# design.net
KiCad netlist of a schematic drawn in Altium Designer
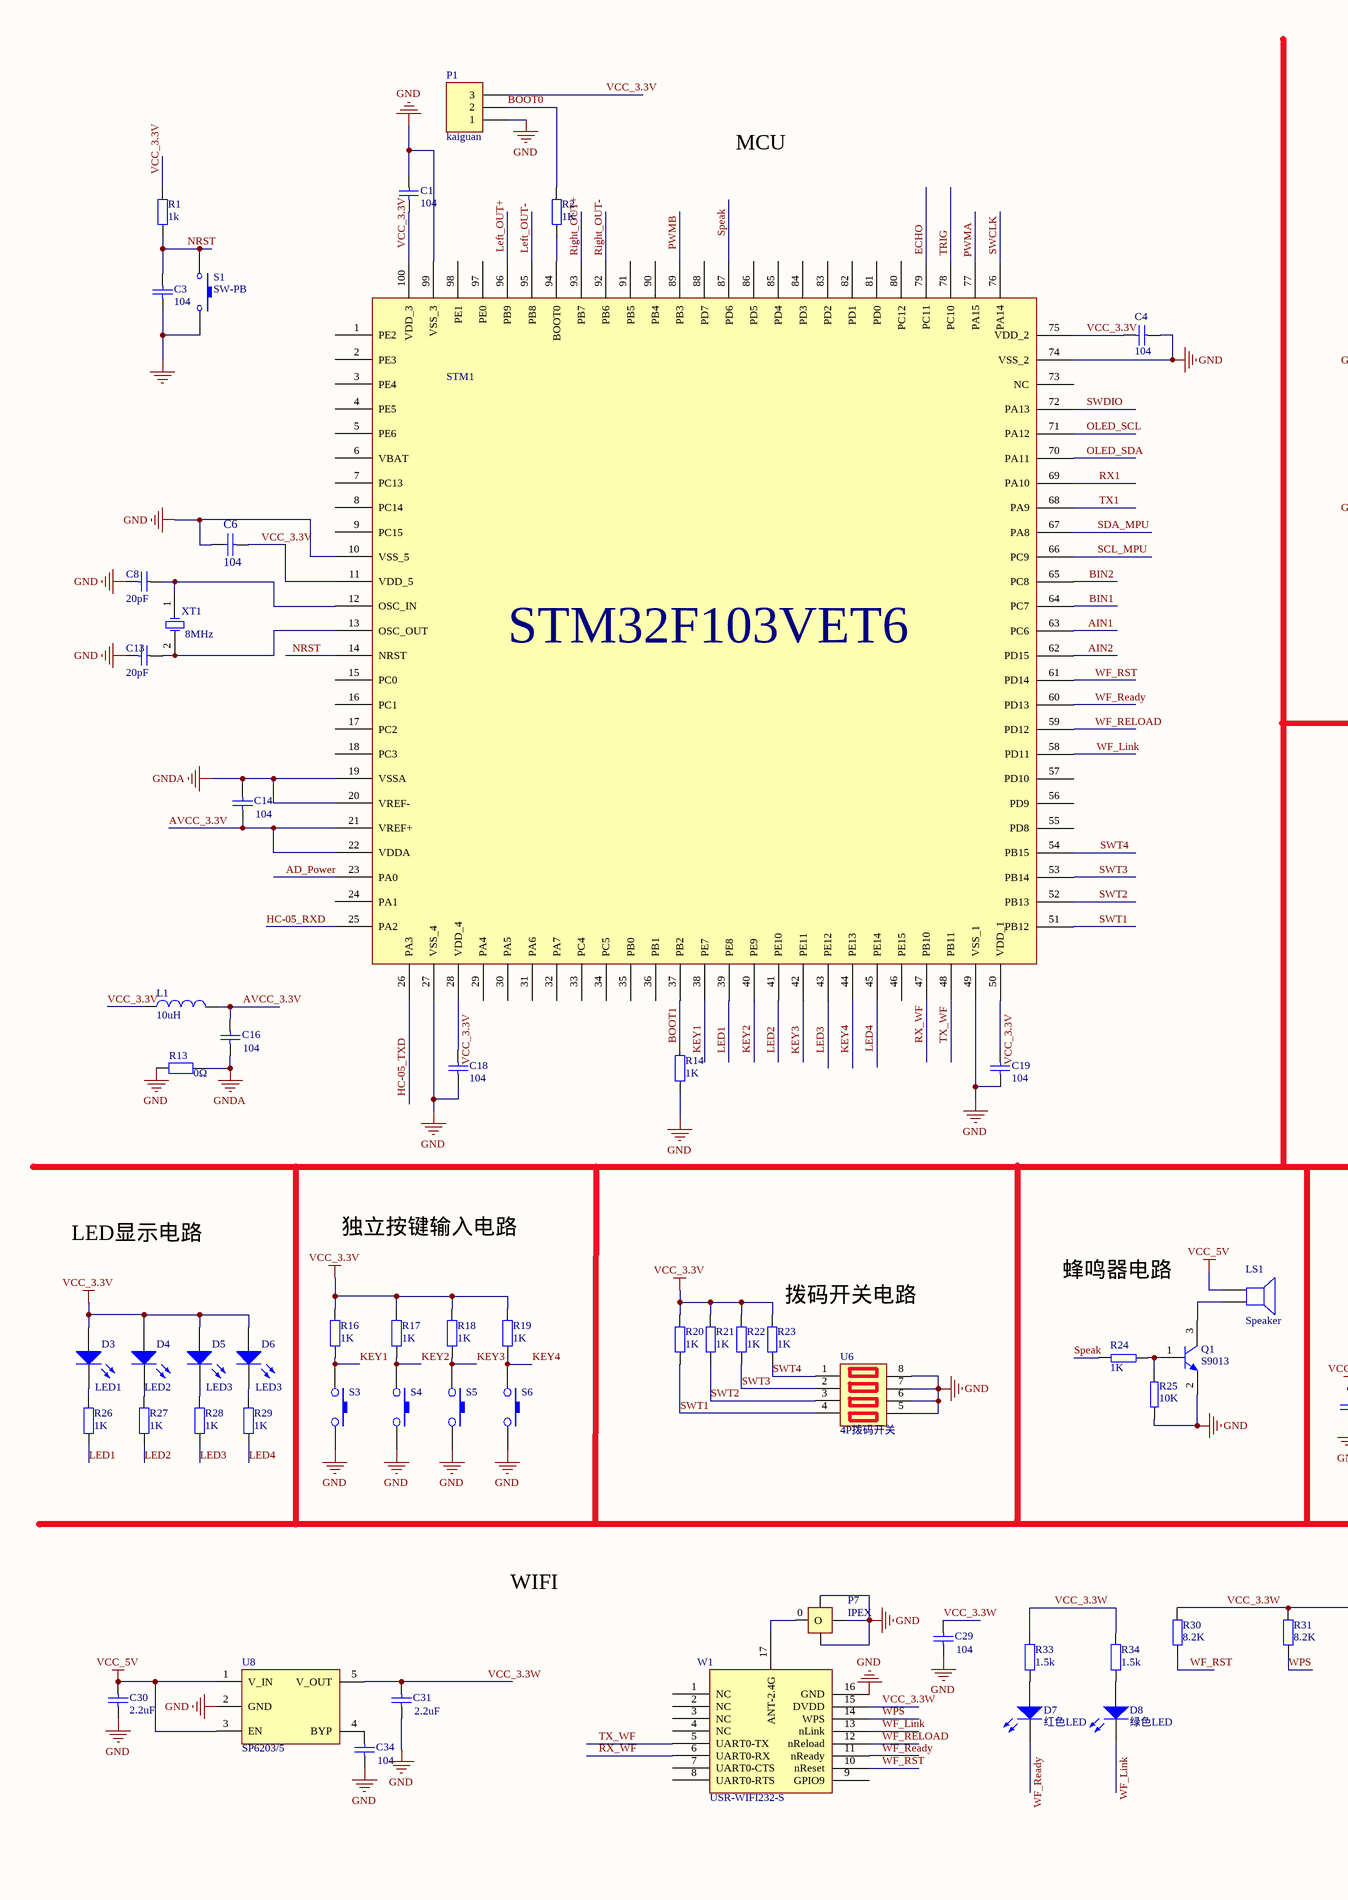
[diagram p0: 平衡车.SchDoc, left]
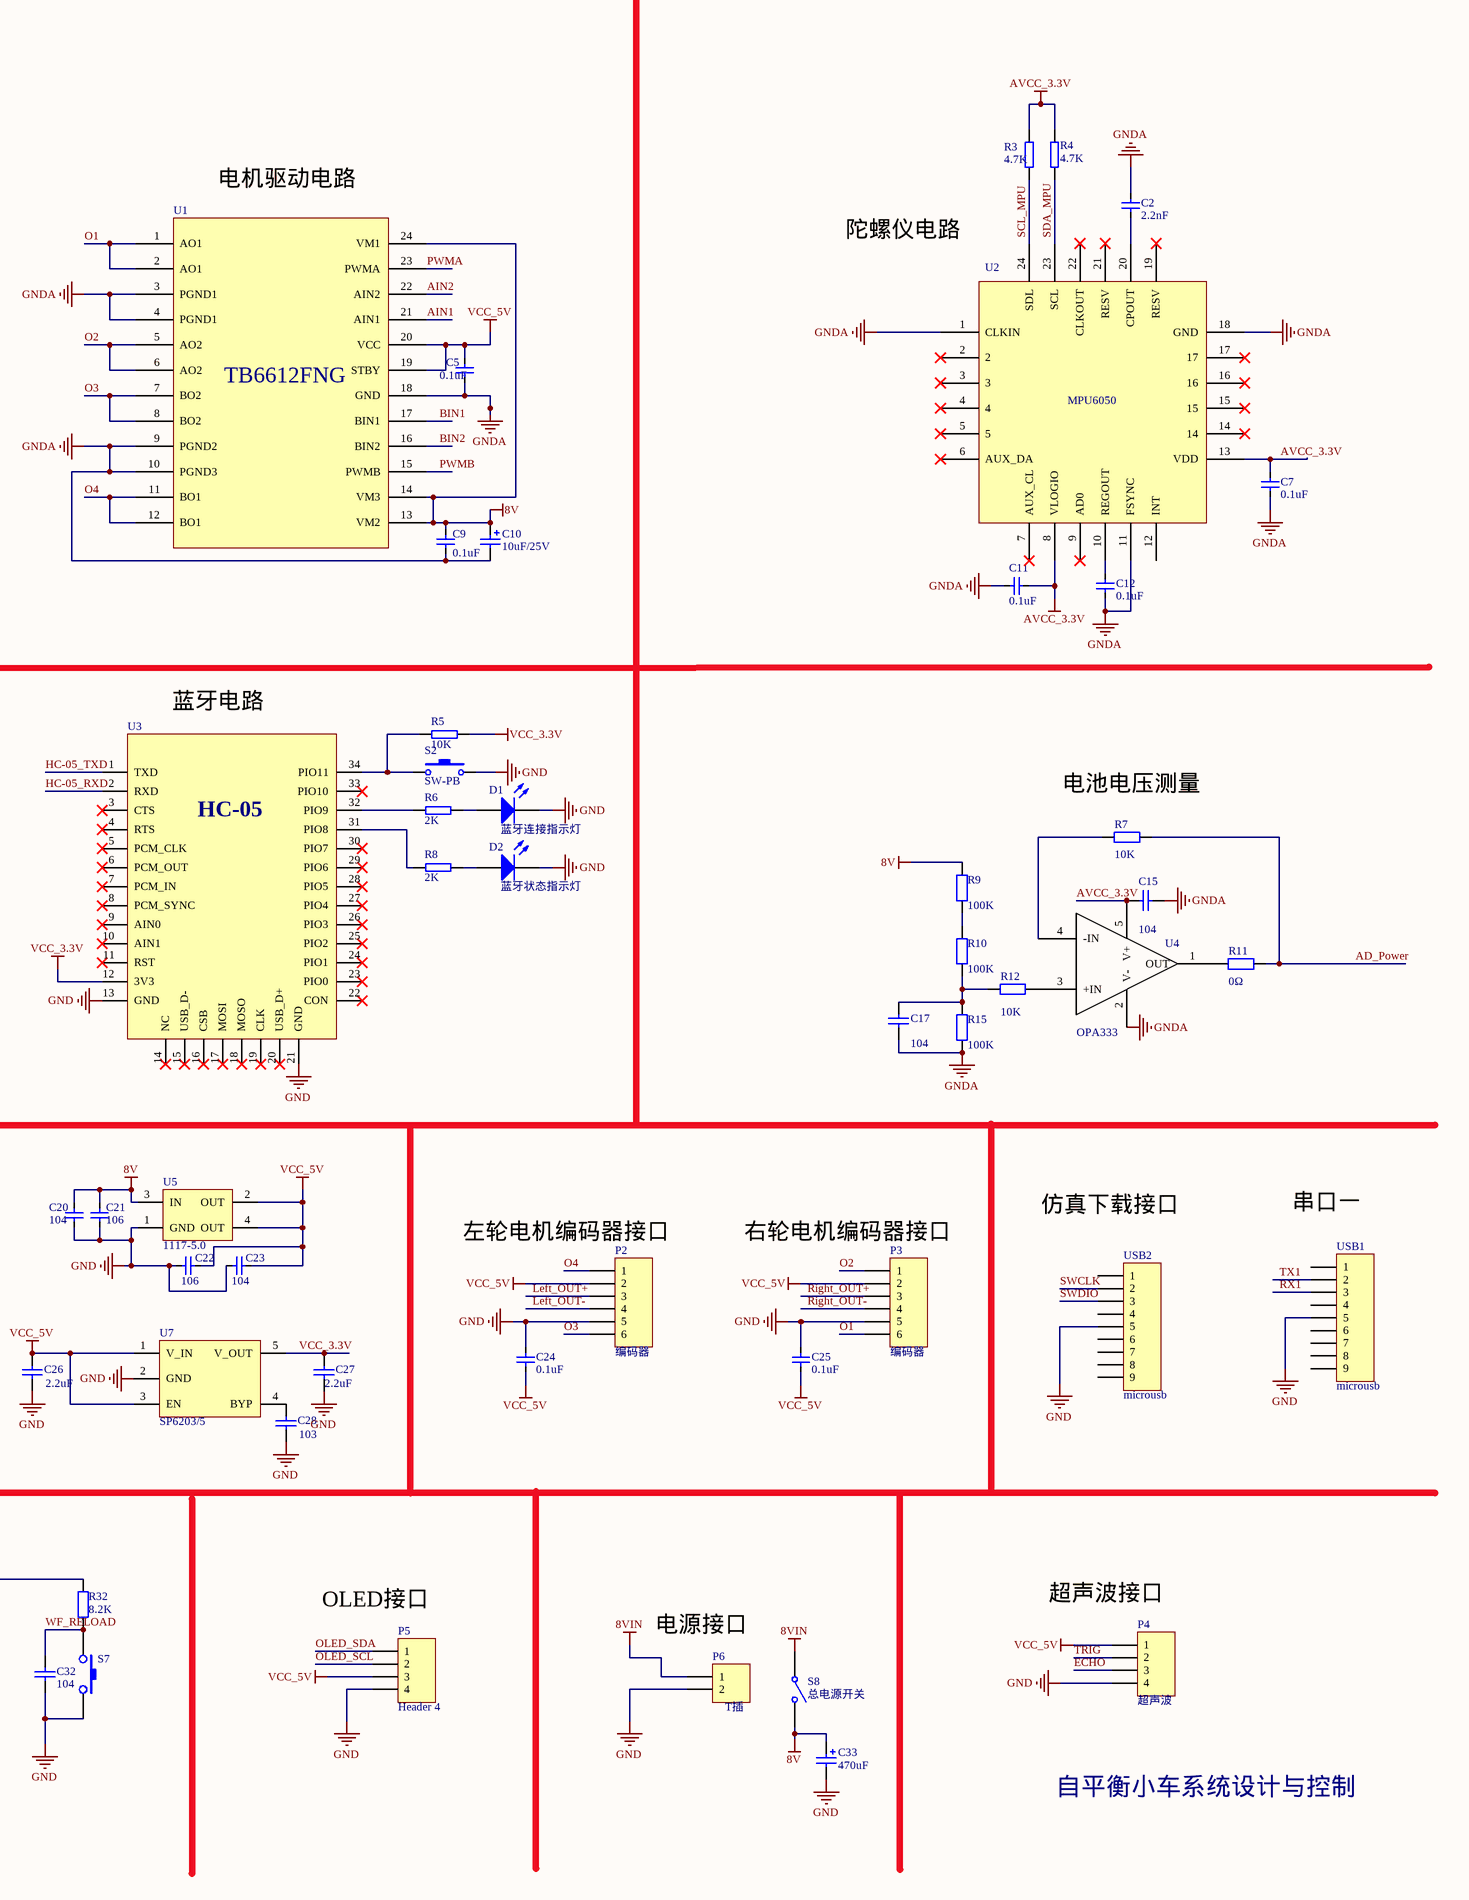
[diagram p1: 平衡车.SchDoc, right]

(export (version "E")
  (design (tool "Eeschema 10.0.6"))
  (components
    (comp (ref "C1")
      (value "104")
      (footprint "0603电容")
      (description "Capacitor")
      (fields (field (name "PUBLISHER") "Altium Limited"))
      (libsource (lib "Miscellaneous Devices") (part "Cap"))
    )
    (comp (ref "C2")
      (value "CAP_2.2nf")
      (footprint "0603电容")
      (fields (field (name "ALTIUM_UNNAMED_1") "2.2nF"))
      (libsource (lib "STM32F103C8T6最小系统") (part "CAP_22"))
    )
    (comp (ref "C3")
      (value "104")
      (footprint "0603电容")
      (description "Capacitor")
      (fields (field (name "PUBLISHER") "Altium Limited"))
      (libsource (lib "Miscellaneous Devices") (part "Cap"))
    )
    (comp (ref "C4")
      (value "104")
      (footprint "0603电容")
      (description "Capacitor")
      (fields (field (name "PUBLISHER") "Altium Limited"))
      (libsource (lib "Miscellaneous Devices") (part "Cap"))
    )
    (comp (ref "C5")
      (value "CAP_104")
      (footprint "0603电容")
      (fields (field (name "ALTIUM_UNNAMED_1") "0.1uF"))
      (libsource (lib "STM32F103C8T6最小系统") (part "CAP_22"))
    )
    (comp (ref "C6") (value "104") (footprint "0603电容") (libsource (lib "*") (part "ProA111.TMP_30p_6")))
    (comp (ref "C7")
      (value "CAP_104")
      (footprint "0603电容")
      (fields (field (name "ALTIUM_UNNAMED_1") "0.1uF"))
      (libsource (lib "STM32F103C8T6最小系统") (part "CAP_22"))
    )
    (comp (ref "C8")
      (value "20pF")
      (footprint "0603电容")
      (description "Capacitor")
      (fields (field (name "PUBLISHER") "Altium Limited"))
      (libsource (lib "Miscellaneous Devices") (part "Cap"))
    )
    (comp (ref "C9")
      (value "CAP_104")
      (footprint "0603电容")
      (fields (field (name "ALTIUM_UNNAMED_1") "0.1uF"))
      (libsource (lib "STM32F103C8T6最小系统") (part "CAP_22"))
    )
    (comp (ref "C10")
      (value "10uF/25V")
      (footprint "C型钽电容")
      (description "Polarized Capacitor (Axial)")
      (fields (field (name "Comment") "Cap Pol2") (field (name "PUBLISHER") "Altium Limited"))
      (libsource (lib "Miscellaneous Devices") (part "Cap Pol2"))
    )
    (comp (ref "C11")
      (value "CAP_104")
      (footprint "0603电容")
      (fields (field (name "ALTIUM_UNNAMED_1") "0.1uF"))
      (libsource (lib "STM32F103C8T6最小系统") (part "CAP_22"))
    )
    (comp (ref "C12")
      (value "CAP_104")
      (footprint "0603电容")
      (fields (field (name "ALTIUM_UNNAMED_1") "0.1uF"))
      (libsource (lib "STM32F103C8T6最小系统") (part "CAP_22"))
    )
    (comp (ref "C13")
      (value "20pF")
      (footprint "0603电容")
      (description "Capacitor")
      (fields (field (name "PUBLISHER") "Altium Limited"))
      (libsource (lib "Miscellaneous Devices") (part "Cap"))
    )
    (comp (ref "C14")
      (value "104")
      (footprint "0603电容")
      (description "Capacitor")
      (fields (field (name "PUBLISHER") "Altium Limited"))
      (libsource (lib "Miscellaneous Devices") (part "Cap"))
    )
    (comp (ref "C15")
      (value "104")
      (footprint "0603电容")
      (description "Capacitor")
      (fields (field (name "PUBLISHER") "Altium Limited"))
      (libsource (lib "Miscellaneous Devices") (part "Cap"))
    )
    (comp (ref "C16")
      (value "104")
      (footprint "0603电容")
      (description "Capacitor")
      (fields (field (name "PUBLISHER") "Altium Limited"))
      (libsource (lib "Miscellaneous Devices") (part "Cap"))
    )
    (comp (ref "C17")
      (value "104")
      (footprint "0603电容")
      (description "Capacitor")
      (fields (field (name "PUBLISHER") "Altium Limited"))
      (libsource (lib "Miscellaneous Devices") (part "Cap"))
    )
    (comp (ref "C18")
      (value "104")
      (footprint "0603电容")
      (description "Capacitor")
      (fields (field (name "PUBLISHER") "Altium Limited"))
      (libsource (lib "Miscellaneous Devices") (part "Cap"))
    )
    (comp (ref "C19")
      (value "104")
      (footprint "0603电容")
      (description "Capacitor")
      (fields (field (name "PUBLISHER") "Altium Limited"))
      (libsource (lib "Miscellaneous Devices") (part "Cap"))
    )
    (comp (ref "C20")
      (value "CAP_104")
      (footprint "0603电容")
      (fields (field (name "ALTIUM_UNNAMED_1") "104"))
      (libsource (lib "STM32F103C8T6最小系统") (part "CAP_22"))
    )
    (comp (ref "C21")
      (value "CAP_104")
      (footprint "0603电容")
      (fields (field (name "ALTIUM_UNNAMED_1") "106"))
      (libsource (lib "STM32F103C8T6最小系统") (part "CAP_22"))
    )
    (comp (ref "C22")
      (value "CAP_104")
      (footprint "0603电容")
      (fields (field (name "ALTIUM_UNNAMED_1") "106"))
      (libsource (lib "STM32F103C8T6最小系统") (part "CAP_22"))
    )
    (comp (ref "C23")
      (value "CAP_104")
      (footprint "0603电容")
      (fields (field (name "ALTIUM_UNNAMED_1") "104"))
      (libsource (lib "STM32F103C8T6最小系统") (part "CAP_22"))
    )
    (comp (ref "C24")
      (value "CAP_104")
      (footprint "0603电容")
      (fields (field (name "ALTIUM_UNNAMED_1") "0.1uF"))
      (libsource (lib "STM32F103C8T6最小系统") (part "CAP_22"))
    )
    (comp (ref "C25")
      (value "CAP_104")
      (footprint "0603电容")
      (fields (field (name "ALTIUM_UNNAMED_1") "0.1uF"))
      (libsource (lib "STM32F103C8T6最小系统") (part "CAP_22"))
    )
    (comp (ref "C26")
      (value "2.2uF")
      (footprint "0603电容")
      (description "Capacitor")
      (fields (field (name "PUBLISHER") "Altium Limited"))
      (libsource (lib "Miscellaneous Devices") (part "Cap"))
    )
    (comp (ref "C27")
      (value "2.2uF")
      (footprint "0603电容")
      (description "Capacitor")
      (fields (field (name "PUBLISHER") "Altium Limited"))
      (libsource (lib "Miscellaneous Devices") (part "Cap"))
    )
    (comp (ref "C28")
      (value "103")
      (footprint "0603电容")
      (description "Capacitor")
      (fields (field (name "PUBLISHER") "Altium Limited"))
      (libsource (lib "Miscellaneous Devices") (part "Cap"))
    )
    (comp (ref "C29")
      (value "104")
      (footprint "0603电容")
      (description "Capacitor")
      (fields (field (name "PUBLISHER") "Altium Limited"))
      (libsource (lib "Miscellaneous Devices") (part "Cap"))
    )
    (comp (ref "C30")
      (value "2.2uF")
      (footprint "0603电容")
      (description "Capacitor")
      (fields (field (name "PUBLISHER") "Altium Limited"))
      (libsource (lib "Miscellaneous Devices") (part "Cap"))
    )
    (comp (ref "C31")
      (value "2.2uF")
      (footprint "0603电容")
      (description "Capacitor")
      (fields (field (name "PUBLISHER") "Altium Limited"))
      (libsource (lib "Miscellaneous Devices") (part "Cap"))
    )
    (comp (ref "C32")
      (value "104")
      (footprint "0603电容")
      (description "Capacitor")
      (fields (field (name "PUBLISHER") "Altium Limited"))
      (libsource (lib "Miscellaneous Devices") (part "Cap"))
    )
    (comp (ref "C33")
      (value "470uF")
      (footprint "470uF")
      (description "Polarized Capacitor (Axial)")
      (fields (field (name "Comment") "Cap Pol2") (field (name "PUBLISHER") "Altium Limited"))
      (libsource (lib "Miscellaneous Devices") (part "Cap Pol2"))
    )
    (comp (ref "C34")
      (value "104")
      (footprint "0603电容")
      (description "Capacitor")
      (fields (field (name "PUBLISHER") "Altium Limited"))
      (libsource (lib "Miscellaneous Devices") (part "Cap"))
    )
    (comp (ref "D1")
      (value "蓝牙连接指示灯")
      (footprint "0603LED红色")
      (description "Typical INFRARED GaAs LED")
      (fields (field (name "PUBLISHER") "Altium Limited"))
      (libsource (lib "Miscellaneous Devices") (part "LED0"))
    )
    (comp (ref "D2")
      (value "蓝牙状态指示灯")
      (footprint "0603LED绿色")
      (description "Typical INFRARED GaAs LED")
      (fields (field (name "PUBLISHER") "Altium Limited"))
      (libsource (lib "Miscellaneous Devices") (part "LED0"))
    )
    (comp (ref "D3")
      (value "LED1")
      (footprint "0603LED红色")
      (description "Typical INFRARED GaAs LED")
      (fields (field (name "PUBLISHER") "Altium Limited"))
      (libsource (lib "Miscellaneous Devices") (part "LED0"))
    )
    (comp (ref "D4")
      (value "LED2")
      (footprint "0603LED红色")
      (description "Typical INFRARED GaAs LED")
      (fields (field (name "PUBLISHER") "Altium Limited"))
      (libsource (lib "Miscellaneous Devices") (part "LED0"))
    )
    (comp (ref "D5")
      (value "LED3")
      (footprint "0603LED红色")
      (description "Typical INFRARED GaAs LED")
      (fields (field (name "PUBLISHER") "Altium Limited"))
      (libsource (lib "Miscellaneous Devices") (part "LED0"))
    )
    (comp (ref "D6")
      (value "LED3")
      (footprint "0603LED红色")
      (description "Typical INFRARED GaAs LED")
      (fields (field (name "PUBLISHER") "Altium Limited"))
      (libsource (lib "Miscellaneous Devices") (part "LED0"))
    )
    (comp (ref "D7")
      (value "红色LED")
      (footprint "0603LED红色")
      (description "Typical INFRARED GaAs LED")
      (fields (field (name "PUBLISHER") "Altium Limited"))
      (libsource (lib "Miscellaneous Devices") (part "LED0"))
    )
    (comp (ref "D8")
      (value "绿色LED")
      (footprint "0603LED绿色")
      (description "Typical INFRARED GaAs LED")
      (fields (field (name "PUBLISHER") "Altium Limited"))
      (libsource (lib "Miscellaneous Devices") (part "LED0"))
    )
    (comp (ref "L1")
      (value "10uH")
      (footprint "电感")
      (description "Inductor")
      (fields (field (name "PUBLISHER") "Altium Limited"))
      (libsource (lib "Miscellaneous Devices") (part "Inductor"))
    )
    (comp (ref "LS1")
      (value "Speaker")
      (footprint "孔距5mm蜂鸣器")
      (description "Loudspeaker")
      (fields (field (name "PUBLISHER") "Altium Limited"))
      (libsource (lib "Miscellaneous Devices") (part "Speaker"))
    )
    (comp (ref "P1")
      (value "kaiguan")
      (footprint "HDR1X3")
      (description "Header, 3-Pin")
      (fields (field (name "PUBLISHER") "Altium Limited"))
      (libsource (lib "Miscellaneous Connectors") (part "Header 3"))
    )
    (comp (ref "P2")
      (value "编码器")
      (footprint "6P带锁插针底座")
      (description "Header, 6-Pin")
      (fields (field (name "PUBLISHER") "Altium Limited"))
      (libsource (lib "Miscellaneous Connectors") (part "Header 6"))
    )
    (comp (ref "P3")
      (value "编码器")
      (footprint "6P带锁插针底座")
      (description "Header, 6-Pin")
      (fields (field (name "PUBLISHER") "Altium Limited"))
      (libsource (lib "Miscellaneous Connectors") (part "Header 6"))
    )
    (comp (ref "P4")
      (value "超声波")
      (footprint "四脚底座")
      (description "Header, 4-Pin")
      (fields (field (name "PUBLISHER") "Altium Limited"))
      (libsource (lib "Miscellaneous Connectors") (part "Header 4"))
    )
    (comp (ref "P5")
      (value "Header 4")
      (footprint "四脚底座_液晶")
      (description "Header, 4-Pin")
      (fields (field (name "PUBLISHER") "Altium Limited"))
      (libsource (lib "Miscellaneous Connectors") (part "Header 4"))
    )
    (comp (ref "P6")
      (value "T插")
      (footprint "电源底座")
      (description "Header, 2-Pin")
      (fields (field (name "PUBLISHER") "Altium Limited"))
      (libsource (lib "Miscellaneous Connectors") (part "Header 2"))
    )
    (comp (ref "P7") (value "IPEX") (footprint "天线底座") (libsource (lib "WZJ_SchLib") (part "IPEX")))
    (comp (ref "Q1") (value "S9013") (footprint "S8050贴片三极管") (libsource (lib "WZJ_SchLib") (part "S9013_s")))
    (comp (ref "R1")
      (value "1k")
      (footprint "0603电阻")
      (description "Resistor")
      (fields (field (name "PUBLISHER") "Altium Limited"))
      (libsource (lib "Miscellaneous Devices") (part "Res2"))
    )
    (comp (ref "R2")
      (value "1K")
      (footprint "0603电阻")
      (description "Resistor")
      (fields (field (name "PUBLISHER") "Altium Limited"))
      (libsource (lib "Miscellaneous Devices") (part "Res2"))
    )
    (comp (ref "R3")
      (value "RES_10K")
      (footprint "0603电阻")
      (fields (field (name "ALTIUM_UNNAMED_1") "4.7K"))
      (libsource (lib "STM32F103C8T6最小系统") (part "RES_10K"))
    )
    (comp (ref "R4")
      (value "RES_10K")
      (footprint "0603电阻")
      (fields (field (name "ALTIUM_UNNAMED_1") "4.7K"))
      (libsource (lib "STM32F103C8T6最小系统") (part "RES_10K"))
    )
    (comp (ref "R5")
      (value "RES_10K")
      (footprint "0603电阻")
      (fields (field (name "ALTIUM_UNNAMED_1") "10K"))
      (libsource (lib "STM32F103C8T6最小系统") (part "RES_10K"))
    )
    (comp (ref "R6")
      (value "RES_10K")
      (footprint "0603电阻")
      (fields (field (name "ALTIUM_UNNAMED_1") "2K"))
      (libsource (lib "STM32F103C8T6最小系统") (part "RES_10K"))
    )
    (comp (ref "R7")
      (value "10K")
      (footprint "0603电阻")
      (description "Resistor")
      (fields (field (name "PUBLISHER") "Altium Limited"))
      (libsource (lib "") (part "Res2_2"))
    )
    (comp (ref "R8")
      (value "RES_10K")
      (footprint "0603电阻")
      (fields (field (name "ALTIUM_UNNAMED_1") "2K"))
      (libsource (lib "STM32F103C8T6最小系统") (part "RES_10K"))
    )
    (comp (ref "R9")
      (value "100K")
      (footprint "0603电阻")
      (description "Resistor")
      (fields (field (name "PUBLISHER") "Altium Limited"))
      (libsource (lib "") (part "Res2_1"))
    )
    (comp (ref "R10")
      (value "100K")
      (footprint "0603电阻")
      (description "Resistor")
      (fields (field (name "PUBLISHER") "Altium Limited"))
      (libsource (lib "") (part "Res2_1"))
    )
    (comp (ref "R11")
      (value "0Ω")
      (footprint "0603电阻")
      (description "Resistor")
      (fields (field (name "PUBLISHER") "Altium Limited"))
      (libsource (lib "") (part "Res2_2"))
    )
    (comp (ref "R12")
      (value "10K")
      (footprint "0603电阻")
      (description "Resistor")
      (fields (field (name "PUBLISHER") "Altium Limited"))
      (libsource (lib "") (part "Res2_2"))
    )
    (comp (ref "R13")
      (value "0Ω")
      (footprint "0603电阻")
      (description "Resistor")
      (fields (field (name "PUBLISHER") "Altium Limited"))
      (libsource (lib "") (part "Res2_2"))
    )
    (comp (ref "R14")
      (value "1K")
      (footprint "0603电阻")
      (description "Resistor")
      (fields (field (name "PUBLISHER") "Altium Limited"))
      (libsource (lib "Miscellaneous Devices") (part "Res2"))
    )
    (comp (ref "R15")
      (value "100K")
      (footprint "0603电阻")
      (description "Resistor")
      (fields (field (name "PUBLISHER") "Altium Limited"))
      (libsource (lib "") (part "Res2_1"))
    )
    (comp (ref "R16")
      (value "1K")
      (footprint "0603电阻")
      (description "Resistor")
      (fields (field (name "PUBLISHER") "Altium Limited"))
      (libsource (lib "") (part "Res2_1"))
    )
    (comp (ref "R17")
      (value "1K")
      (footprint "0603电阻")
      (description "Resistor")
      (fields (field (name "PUBLISHER") "Altium Limited"))
      (libsource (lib "") (part "Res2_1"))
    )
    (comp (ref "R18")
      (value "1K")
      (footprint "0603电阻")
      (description "Resistor")
      (fields (field (name "PUBLISHER") "Altium Limited"))
      (libsource (lib "") (part "Res2_1"))
    )
    (comp (ref "R19")
      (value "1K")
      (footprint "0603电阻")
      (description "Resistor")
      (fields (field (name "PUBLISHER") "Altium Limited"))
      (libsource (lib "Miscellaneous Devices") (part "Res2"))
    )
    (comp (ref "R20")
      (value "1K")
      (footprint "0603电阻")
      (description "Resistor")
      (fields (field (name "PUBLISHER") "Altium Limited"))
      (libsource (lib "") (part "Res2_1"))
    )
    (comp (ref "R21")
      (value "1K")
      (footprint "0603电阻")
      (description "Resistor")
      (fields (field (name "PUBLISHER") "Altium Limited"))
      (libsource (lib "") (part "Res2_1"))
    )
    (comp (ref "R22")
      (value "1K")
      (footprint "0603电阻")
      (description "Resistor")
      (fields (field (name "PUBLISHER") "Altium Limited"))
      (libsource (lib "") (part "Res2_1"))
    )
    (comp (ref "R23")
      (value "1K")
      (footprint "0603电阻")
      (description "Resistor")
      (fields (field (name "PUBLISHER") "Altium Limited"))
      (libsource (lib "Miscellaneous Devices") (part "Res2"))
    )
    (comp (ref "R24")
      (value "RES_10K")
      (footprint "0603电阻")
      (fields (field (name "ALTIUM_UNNAMED_1") "1K"))
      (libsource (lib "STM32F103C8T6最小系统") (part "RES_10K"))
    )
    (comp (ref "R25")
      (value "RES_10K")
      (footprint "0603电阻")
      (fields (field (name "ALTIUM_UNNAMED_1") "10K"))
      (libsource (lib "STM32F103C8T6最小系统") (part "RES_10K"))
    )
    (comp (ref "R26")
      (value "1K")
      (footprint "0603电阻")
      (description "Resistor")
      (fields (field (name "PUBLISHER") "Altium Limited"))
      (libsource (lib "") (part "Res2_1"))
    )
    (comp (ref "R27")
      (value "1K")
      (footprint "0603电阻")
      (description "Resistor")
      (fields (field (name "PUBLISHER") "Altium Limited"))
      (libsource (lib "") (part "Res2_1"))
    )
    (comp (ref "R28")
      (value "1K")
      (footprint "0603电阻")
      (description "Resistor")
      (fields (field (name "PUBLISHER") "Altium Limited"))
      (libsource (lib "") (part "Res2_1"))
    )
    (comp (ref "R29")
      (value "1K")
      (footprint "0603电阻")
      (description "Resistor")
      (fields (field (name "PUBLISHER") "Altium Limited"))
      (libsource (lib "") (part "Res2_1"))
    )
    (comp (ref "R30")
      (value "8.2K")
      (footprint "0603电阻")
      (description "Resistor")
      (fields (field (name "PUBLISHER") "Altium Limited"))
      (libsource (lib "Miscellaneous Devices") (part "Res2"))
    )
    (comp (ref "R31")
      (value "8.2K")
      (footprint "0603电阻")
      (description "Resistor")
      (fields (field (name "PUBLISHER") "Altium Limited"))
      (libsource (lib "Miscellaneous Devices") (part "Res2"))
    )
    (comp (ref "R32")
      (value "8.2K")
      (footprint "0603电阻")
      (description "Resistor")
      (fields (field (name "PUBLISHER") "Altium Limited"))
      (libsource (lib "Miscellaneous Devices") (part "Res2"))
    )
    (comp (ref "R33")
      (value "1.5k")
      (footprint "0603电阻")
      (description "Resistor")
      (fields (field (name "PUBLISHER") "Altium Limited"))
      (libsource (lib "") (part "Res2_1"))
    )
    (comp (ref "R34")
      (value "1.5k")
      (footprint "0603电阻")
      (description "Resistor")
      (fields (field (name "PUBLISHER") "Altium Limited"))
      (libsource (lib "") (part "Res2_1"))
    )
    (comp (ref "S1")
      (value "SW-PB")
      (footprint "贴片按键")
      (description "Switch")
      (fields (field (name "PUBLISHER") "Altium Limited"))
      (libsource (lib "Miscellaneous Devices") (part "SW-PB"))
    )
    (comp (ref "S2")
      (value "SW-PB")
      (footprint "贴片按键")
      (description "Switch")
      (fields (field (name "PUBLISHER") "Altium Limited"))
      (libsource (lib "SCH_Switch") (part "SW-PB"))
    )
    (comp (ref "S3") (value "SW-PB") (footprint "贴片按键") (libsource (lib "STM32F103C8T6最小系统") (part "SW-PB")))
    (comp (ref "S4") (value "SW-PB") (footprint "贴片按键") (libsource (lib "STM32F103C8T6最小系统") (part "SW-PB")))
    (comp (ref "S5") (value "SW-PB") (footprint "贴片按键") (libsource (lib "STM32F103C8T6最小系统") (part "SW-PB")))
    (comp (ref "S6") (value "SW-PB") (footprint "贴片按键") (libsource (lib "STM32F103C8T6最小系统") (part "SW-PB")))
    (comp (ref "S7") (value "SW-PB") (footprint "贴片按键") (libsource (lib "STM32F103C8T6最小系统") (part "SW-PB")))
    (comp (ref "S8")
      (value "总电源开关")
      (footprint "纽子开关")
      (description "Single-Pole, Single-Throw Switch")
      (fields (field (name "PUBLISHER") "Altium Limited"))
      (libsource (lib "Miscellaneous Devices") (part "SW-SPST"))
    )
    (comp (ref "STM1")
      (value "STM32F103VET6")
      (footprint "LQFP 100")
      (libsource (lib "WZJ_SchLib") (part "STM32F103VET6"))
    )
    (comp (ref "U1")
      (value "TB6612FNG")
      (footprint "TB6612")
      (libsource (lib "xl_lib_v_1") (part "TB6612FNG"))
    )
    (comp (ref "U2")
      (value "MPU6050")
      (footprint "MPU6050_3mm")
      (libsource (lib "xl_lib_v_1") (part "MPU6050"))
    )
    (comp (ref "U3") (value "HC-05蓝牙") (footprint "HC-05蓝牙邮票孔") (libsource (lib "自平衡小车") (part "HC-05蓝牙")))
    (comp (ref "U4") (value "OPA333") (footprint "LM2735") (libsource (lib "WZJ_SchLib") (part "OPA333")))
    (comp (ref "U5") (value "1117-5.0") (footprint "1117稳压") (libsource (lib "自平衡小车") (part "1117")))
    (comp (ref "U6") (value "4P拨码开关") (footprint "4P贴片拨码开关") (libsource (lib "我的大学四年自画AD库") (part "4P拨码开关")))
    (comp (ref "U7") (value "SP6203/5") (footprint "LM2735") (libsource (lib "WZJ_SchLib") (part "SP6203/5")))
    (comp (ref "U8") (value "SP6203/5") (footprint "LM2735") (libsource (lib "WZJ_SchLib") (part "SP6203/5")))
    (comp (ref "USB1")
      (value "microusb")
      (footprint "Microusb")
      (description "Header, 9-Pin")
      (fields (field (name "PUBLISHER") "Altium Limited"))
      (libsource (lib "Miscellaneous Connectors") (part "Header 9"))
    )
    (comp (ref "USB2")
      (value "microusb")
      (footprint "Microusb")
      (description "Header, 9-Pin")
      (fields (field (name "PUBLISHER") "Altium Limited"))
      (libsource (lib "Miscellaneous Connectors") (part "Header 9"))
    )
    (comp (ref "W1")
      (value "USR-WIFI232-S")
      (footprint "WIFI")
      (libsource (lib "USR-WIFI232-S_sch") (part "USR-WIFI232-S"))
    )
    (comp (ref "XT1")
      (value "8MHz")
      (footprint "两脚贴片晶振")
      (description "Crystal Oscillator")
      (fields (field (name "PUBLISHER") "Altium Limited"))
      (libsource (lib "Miscellaneous Devices") (part "XTAL"))
    )
  )
  (nets
    (net (code "1") (name "/AD_Power") (class "Default")
      (node (ref "R11") (pin "2") (pinfunction "2_2") (pintype "passive"))
      (node (ref "R7") (pin "2") (pinfunction "2_2") (pintype "passive"))
      (node (ref "STM1") (pin "23") (pinfunction "PA0_23") (pintype "passive"))
    )
    (net (code "2") (name "/AIN1") (class "Default")
      (node (ref "STM1") (pin "63") (pinfunction "PC6_63") (pintype "passive"))
      (node (ref "U1") (pin "21") (pinfunction "AIN1_21") (pintype "passive"))
    )
    (net (code "3") (name "/AIN2") (class "Default")
      (node (ref "STM1") (pin "62") (pinfunction "PD15_62") (pintype "passive"))
      (node (ref "U1") (pin "22") (pinfunction "AIN2_22") (pintype "passive"))
    )
    (net (code "4") (name "/BIN1") (class "Default")
      (node (ref "STM1") (pin "64") (pinfunction "PC7_64") (pintype "passive"))
      (node (ref "U1") (pin "17") (pinfunction "BIN1_17") (pintype "passive"))
    )
    (net (code "5") (name "/BIN2") (class "Default")
      (node (ref "STM1") (pin "65") (pinfunction "PC8_65") (pintype "passive"))
      (node (ref "U1") (pin "16") (pinfunction "BIN2_16") (pintype "passive"))
    )
    (net (code "6") (name "/BOOT0") (class "Default")
      (node (ref "P1") (pin "2") (pinfunction "2_2") (pintype "passive"))
      (node (ref "R2") (pin "1") (pinfunction "1_1") (pintype "passive"))
    )
    (net (code "7") (name "/BOOT1") (class "Default")
      (node (ref "R14") (pin "1") (pinfunction "1_1") (pintype "passive"))
      (node (ref "STM1") (pin "37") (pinfunction "PB2_37") (pintype "passive"))
    )
    (net (code "8") (name "/ECHO") (class "Default")
      (node (ref "P4") (pin "3") (pinfunction "3_3") (pintype "passive"))
      (node (ref "STM1") (pin "79") (pinfunction "PC11_79") (pintype "passive"))
    )
    (net (code "9") (name "/HC-05_RXD") (class "Default")
      (node (ref "STM1") (pin "25") (pinfunction "PA2_25") (pintype "passive"))
      (node (ref "U3") (pin "2") (pinfunction "RXD_2") (pintype "passive"))
    )
    (net (code "10") (name "/HC-05_TXD") (class "Default")
      (node (ref "STM1") (pin "26") (pinfunction "PA3_26") (pintype "passive"))
      (node (ref "U3") (pin "1") (pinfunction "TXD_1") (pintype "passive"))
    )
    (net (code "11") (name "/KEY1") (class "Default")
      (node (ref "R16") (pin "1") (pinfunction "1_1") (pintype "passive"))
      (node (ref "S3") (pin "1") (pinfunction "1_1") (pintype "passive"))
      (node (ref "STM1") (pin "38") (pinfunction "PE7_38") (pintype "passive"))
    )
    (net (code "12") (name "/KEY2") (class "Default")
      (node (ref "R17") (pin "1") (pinfunction "1_1") (pintype "passive"))
      (node (ref "S4") (pin "1") (pinfunction "1_1") (pintype "passive"))
      (node (ref "STM1") (pin "40") (pinfunction "PE9_40") (pintype "passive"))
    )
    (net (code "13") (name "/KEY3") (class "Default")
      (node (ref "R18") (pin "1") (pinfunction "1_1") (pintype "passive"))
      (node (ref "S5") (pin "1") (pinfunction "1_1") (pintype "passive"))
      (node (ref "STM1") (pin "42") (pinfunction "PE11_42") (pintype "passive"))
    )
    (net (code "14") (name "/KEY4") (class "Default")
      (node (ref "R19") (pin "2") (pinfunction "2_2") (pintype "passive"))
      (node (ref "S6") (pin "1") (pinfunction "1_1") (pintype "passive"))
      (node (ref "STM1") (pin "44") (pinfunction "PE13_44") (pintype "passive"))
    )
    (net (code "15") (name "/LED1") (class "Default")
      (node (ref "R26") (pin "1") (pinfunction "1_1") (pintype "passive"))
      (node (ref "STM1") (pin "39") (pinfunction "PE8_39") (pintype "passive"))
    )
    (net (code "16") (name "/LED2") (class "Default")
      (node (ref "R27") (pin "1") (pinfunction "1_1") (pintype "passive"))
      (node (ref "STM1") (pin "41") (pinfunction "PE10_41") (pintype "passive"))
    )
    (net (code "17") (name "/LED3") (class "Default")
      (node (ref "R28") (pin "1") (pinfunction "1_1") (pintype "passive"))
      (node (ref "STM1") (pin "43") (pinfunction "PE12_43") (pintype "passive"))
    )
    (net (code "18") (name "/LED4") (class "Default")
      (node (ref "R29") (pin "1") (pinfunction "1_1") (pintype "passive"))
      (node (ref "STM1") (pin "45") (pinfunction "PE14_45") (pintype "passive"))
    )
    (net (code "19") (name "/Left_OUT+") (class "Default")
      (node (ref "P2") (pin "3") (pinfunction "3_3") (pintype "passive"))
      (node (ref "STM1") (pin "96") (pinfunction "PB9_96") (pintype "passive"))
    )
    (net (code "20") (name "/Left_OUT-") (class "Default")
      (node (ref "P2") (pin "4") (pinfunction "4_4") (pintype "passive"))
      (node (ref "STM1") (pin "95") (pinfunction "PB8_95") (pintype "passive"))
    )
    (net (code "21") (name "/NRST") (class "Default")
      (node (ref "C3") (pin "2") (pinfunction "2_2") (pintype "passive"))
      (node (ref "R1") (pin "2") (pinfunction "2_2") (pintype "passive"))
      (node (ref "S1") (pin "1") (pinfunction "1_1") (pintype "passive"))
      (node (ref "STM1") (pin "14") (pinfunction "NRST_14") (pintype "passive"))
    )
    (net (code "22") (name "/O1") (class "Default")
      (node (ref "P3") (pin "6") (pinfunction "6_6") (pintype "passive"))
      (node (ref "U1") (pin "1") (pinfunction "AO1_1") (pintype "passive"))
      (node (ref "U1") (pin "2") (pinfunction "AO1_2") (pintype "passive"))
    )
    (net (code "23") (name "/O2") (class "Default")
      (node (ref "P3") (pin "1") (pinfunction "1_1") (pintype "passive"))
      (node (ref "U1") (pin "5") (pinfunction "AO2_5") (pintype "passive"))
      (node (ref "U1") (pin "6") (pinfunction "AO2_6") (pintype "passive"))
    )
    (net (code "24") (name "/O3") (class "Default")
      (node (ref "P2") (pin "6") (pinfunction "6_6") (pintype "passive"))
      (node (ref "U1") (pin "7") (pinfunction "BO2_7") (pintype "passive"))
      (node (ref "U1") (pin "8") (pinfunction "BO2_8") (pintype "passive"))
    )
    (net (code "25") (name "/O4") (class "Default")
      (node (ref "P2") (pin "1") (pinfunction "1_1") (pintype "passive"))
      (node (ref "U1") (pin "11") (pinfunction "BO1_11") (pintype "passive"))
      (node (ref "U1") (pin "12") (pinfunction "BO1_12") (pintype "passive"))
    )
    (net (code "26") (name "/OLED_SCL") (class "Default")
      (node (ref "P5") (pin "2") (pinfunction "2_2") (pintype "passive"))
      (node (ref "STM1") (pin "71") (pinfunction "PA12_71") (pintype "passive"))
    )
    (net (code "27") (name "/OLED_SDA") (class "Default")
      (node (ref "P5") (pin "1") (pinfunction "1_1") (pintype "passive"))
      (node (ref "STM1") (pin "70") (pinfunction "PA11_70") (pintype "passive"))
    )
    (net (code "28") (name "/PWMA") (class "Default")
      (node (ref "STM1") (pin "77") (pinfunction "PA15_77") (pintype "passive"))
      (node (ref "U1") (pin "23") (pinfunction "PWMA_23") (pintype "passive"))
    )
    (net (code "29") (name "/PWMB") (class "Default")
      (node (ref "STM1") (pin "89") (pinfunction "PB3_89") (pintype "passive"))
      (node (ref "U1") (pin "15") (pinfunction "PWMB_15") (pintype "passive"))
    )
    (net (code "30") (name "/RX1") (class "Default")
      (node (ref "STM1") (pin "69") (pinfunction "PA10_69") (pintype "passive"))
      (node (ref "USB1") (pin "3") (pinfunction "3_3") (pintype "passive"))
    )
    (net (code "31") (name "/RX_WF") (class "Default")
      (node (ref "STM1") (pin "47") (pinfunction "PB10_47") (pintype "passive"))
      (node (ref "W1") (pin "6") (pinfunction "UART0-RX_6") (pintype "passive"))
    )
    (net (code "32") (name "/Right_OUT+") (class "Default")
      (node (ref "P3") (pin "3") (pinfunction "3_3") (pintype "passive"))
      (node (ref "STM1") (pin "93") (pinfunction "PB7_93") (pintype "passive"))
    )
    (net (code "33") (name "/Right_OUT-") (class "Default")
      (node (ref "P3") (pin "4") (pinfunction "4_4") (pintype "passive"))
      (node (ref "STM1") (pin "92") (pinfunction "PB6_92") (pintype "passive"))
    )
    (net (code "34") (name "/SCL_MPU") (class "Default")
      (node (ref "R3") (pin "1") (pintype "passive"))
      (node (ref "STM1") (pin "66") (pinfunction "PC9_66") (pintype "passive"))
      (node (ref "U2") (pin "24") (pinfunction "SDL_24") (pintype "passive"))
    )
    (net (code "35") (name "/SDA_MPU") (class "Default")
      (node (ref "R4") (pin "1") (pintype "passive"))
      (node (ref "STM1") (pin "67") (pinfunction "PA8_67") (pintype "passive"))
      (node (ref "U2") (pin "23") (pinfunction "SCL_23") (pintype "passive"))
    )
    (net (code "36") (name "/SWCLK") (class "Default")
      (node (ref "STM1") (pin "76") (pinfunction "PA14_76") (pintype "passive"))
      (node (ref "USB2") (pin "2") (pinfunction "2_2") (pintype "passive"))
    )
    (net (code "37") (name "/SWDIO") (class "Default")
      (node (ref "STM1") (pin "72") (pinfunction "PA13_72") (pintype "passive"))
      (node (ref "USB2") (pin "3") (pinfunction "3_3") (pintype "passive"))
    )
    (net (code "38") (name "/SWT1") (class "Default")
      (node (ref "R20") (pin "1") (pinfunction "1_1") (pintype "passive"))
      (node (ref "STM1") (pin "51") (pinfunction "PB12_51") (pintype "passive"))
      (node (ref "U6") (pin "4") (pintype "passive"))
    )
    (net (code "39") (name "/SWT2") (class "Default")
      (node (ref "R21") (pin "1") (pinfunction "1_1") (pintype "passive"))
      (node (ref "STM1") (pin "52") (pinfunction "PB13_52") (pintype "passive"))
      (node (ref "U6") (pin "3") (pintype "passive"))
    )
    (net (code "40") (name "/SWT3") (class "Default")
      (node (ref "R22") (pin "1") (pinfunction "1_1") (pintype "passive"))
      (node (ref "STM1") (pin "53") (pinfunction "PB14_53") (pintype "passive"))
      (node (ref "U6") (pin "2") (pintype "passive"))
    )
    (net (code "41") (name "/SWT4") (class "Default")
      (node (ref "R23") (pin "2") (pinfunction "2_2") (pintype "passive"))
      (node (ref "STM1") (pin "54") (pinfunction "PB15_54") (pintype "passive"))
      (node (ref "U6") (pin "1") (pintype "passive"))
    )
    (net (code "42") (name "/Speak") (class "Default")
      (node (ref "R24") (pin "1") (pintype "passive"))
      (node (ref "STM1") (pin "87") (pinfunction "PD6_87") (pintype "passive"))
    )
    (net (code "43") (name "/TRIG") (class "Default")
      (node (ref "P4") (pin "2") (pinfunction "2_2") (pintype "passive"))
      (node (ref "STM1") (pin "78") (pinfunction "PC10_78") (pintype "passive"))
    )
    (net (code "44") (name "/TX1") (class "Default")
      (node (ref "STM1") (pin "68") (pinfunction "PA9_68") (pintype "passive"))
      (node (ref "USB1") (pin "2") (pinfunction "2_2") (pintype "passive"))
    )
    (net (code "45") (name "/TX_WF") (class "Default")
      (node (ref "STM1") (pin "48") (pinfunction "PB11_48") (pintype "passive"))
      (node (ref "W1") (pin "5") (pinfunction "UART0-TX_5") (pintype "passive"))
    )
    (net (code "46") (name "/VCC_3.3W") (class "Default")
      (node (ref "C29") (pin "2") (pinfunction "2_2") (pintype "passive"))
      (node (ref "C31") (pin "2") (pinfunction "2_2") (pintype "passive"))
      (node (ref "R30") (pin "1") (pinfunction "1_1") (pintype "passive"))
      (node (ref "R31") (pin "1") (pinfunction "1_1") (pintype "passive"))
      (node (ref "R32") (pin "1") (pinfunction "1_1") (pintype "passive"))
      (node (ref "R33") (pin "2") (pinfunction "2_2") (pintype "passive"))
      (node (ref "R34") (pin "2") (pinfunction "2_2") (pintype "passive"))
      (node (ref "U8") (pin "5") (pinfunction "V_OUT_5") (pintype "passive"))
      (node (ref "W1") (pin "15") (pinfunction "DVDD_15") (pintype "passive"))
    )
    (net (code "47") (name "/WF_Link") (class "Default")
      (node (ref "D8") (pin "2") (pinfunction "K_2") (pintype "passive"))
      (node (ref "STM1") (pin "58") (pinfunction "PD11_58") (pintype "passive"))
      (node (ref "W1") (pin "13") (pinfunction "nLink_13") (pintype "passive"))
    )
    (net (code "48") (name "/WF_RELOAD") (class "Default")
      (node (ref "C32") (pin "2") (pinfunction "2_2") (pintype "passive"))
      (node (ref "R32") (pin "2") (pinfunction "2_2") (pintype "passive"))
      (node (ref "S7") (pin "1") (pinfunction "1_1") (pintype "passive"))
      (node (ref "STM1") (pin "59") (pinfunction "PD12_59") (pintype "passive"))
      (node (ref "W1") (pin "12") (pinfunction "nReload_12") (pintype "passive"))
    )
    (net (code "49") (name "/WF_RST") (class "Default")
      (node (ref "R30") (pin "2") (pinfunction "2_2") (pintype "passive"))
      (node (ref "STM1") (pin "61") (pinfunction "PD14_61") (pintype "passive"))
      (node (ref "W1") (pin "10") (pinfunction "nReset_10") (pintype "passive"))
    )
    (net (code "50") (name "/WF_Ready") (class "Default")
      (node (ref "D7") (pin "2") (pinfunction "K_2") (pintype "passive"))
      (node (ref "STM1") (pin "60") (pinfunction "PD13_60") (pintype "passive"))
      (node (ref "W1") (pin "11") (pinfunction "nReady_11") (pintype "passive"))
    )
    (net (code "51") (name "/WPS") (class "Default")
      (node (ref "R31") (pin "2") (pinfunction "2_2") (pintype "passive"))
      (node (ref "W1") (pin "14") (pinfunction "WPS_14") (pintype "passive"))
    )
    (net (code "52") (name "8V") (class "Default")
      (node (ref "C10") (pin "1") (pinfunction "1_1") (pintype "passive"))
      (node (ref "C20") (pin "2") (pintype "passive"))
      (node (ref "C21") (pin "2") (pintype "passive"))
      (node (ref "C33") (pin "1") (pinfunction "1_1") (pintype "passive"))
      (node (ref "C9") (pin "2") (pintype "passive"))
      (node (ref "R9") (pin "2") (pinfunction "2_2") (pintype "passive"))
      (node (ref "S8") (pin "2") (pinfunction "NO_2") (pintype "passive"))
      (node (ref "U1") (pin "13") (pinfunction "VM2_13") (pintype "passive"))
      (node (ref "U1") (pin "14") (pinfunction "VM3_14") (pintype "passive"))
      (node (ref "U1") (pin "24") (pinfunction "VM1_24") (pintype "passive"))
      (node (ref "U5") (pin "3") (pinfunction "IN_3") (pintype "passive"))
    )
    (net (code "53") (name "8VIN") (class "Default")
      (node (ref "P6") (pin "1") (pinfunction "1_1") (pintype "passive"))
      (node (ref "S8") (pin "1") (pinfunction "COMMON_1") (pintype "passive"))
    )
    (net (code "54") (name "AVCC_3.3V") (class "Default")
      (node (ref "C11") (pin "2") (pintype "passive"))
      (node (ref "C14") (pin "1") (pinfunction "1_1") (pintype "passive"))
      (node (ref "C15") (pin "2") (pinfunction "2_2") (pintype "passive"))
      (node (ref "C16") (pin "2") (pinfunction "2_2") (pintype "passive"))
      (node (ref "C7") (pin "2") (pintype "passive"))
      (node (ref "L1") (pin "2") (pinfunction "2_2") (pintype "passive"))
      (node (ref "R3") (pin "2") (pintype "passive"))
      (node (ref "R4") (pin "2") (pintype "passive"))
      (node (ref "STM1") (pin "21") (pinfunction "VREF+_21") (pintype "passive"))
      (node (ref "STM1") (pin "22") (pinfunction "VDDA_22") (pintype "passive"))
      (node (ref "U2") (pin "13") (pinfunction "VDD_13") (pintype "passive"))
      (node (ref "U2") (pin "8") (pinfunction "VLOGIO_8") (pintype "passive"))
      (node (ref "U4") (pin "5") (pinfunction "V+_5") (pintype "passive"))
    )
    (net (code "55") (name "GND") (class "Default")
      (node (ref "C1") (pin "2") (pinfunction "2_2") (pintype "passive"))
      (node (ref "C13") (pin "1") (pinfunction "1_1") (pintype "passive"))
      (node (ref "C18") (pin "1") (pinfunction "1_1") (pintype "passive"))
      (node (ref "C19") (pin "1") (pinfunction "1_1") (pintype "passive"))
      (node (ref "C20") (pin "1") (pintype "passive"))
      (node (ref "C21") (pin "1") (pintype "passive"))
      (node (ref "C22") (pin "2") (pintype "passive"))
      (node (ref "C23") (pin "1") (pintype "passive"))
      (node (ref "C24") (pin "1") (pintype "passive"))
      (node (ref "C25") (pin "1") (pintype "passive"))
      (node (ref "C26") (pin "1") (pinfunction "1_1") (pintype "passive"))
      (node (ref "C27") (pin "1") (pinfunction "1_1") (pintype "passive"))
      (node (ref "C28") (pin "1") (pinfunction "1_1") (pintype "passive"))
      (node (ref "C29") (pin "1") (pinfunction "1_1") (pintype "passive"))
      (node (ref "C3") (pin "1") (pinfunction "1_1") (pintype "passive"))
      (node (ref "C30") (pin "1") (pinfunction "1_1") (pintype "passive"))
      (node (ref "C31") (pin "1") (pinfunction "1_1") (pintype "passive"))
      (node (ref "C32") (pin "1") (pinfunction "1_1") (pintype "passive"))
      (node (ref "C33") (pin "2") (pinfunction "2_2") (pintype "passive"))
      (node (ref "C34") (pin "1") (pinfunction "1_1") (pintype "passive"))
      (node (ref "C4") (pin "1") (pinfunction "1_1") (pintype "passive"))
      (node (ref "C6") (pin "2") (pintype "passive"))
      (node (ref "C8") (pin "1") (pinfunction "1_1") (pintype "passive"))
      (node (ref "D1") (pin "2") (pinfunction "K_2") (pintype "passive"))
      (node (ref "D2") (pin "2") (pinfunction "K_2") (pintype "passive"))
      (node (ref "P1") (pin "1") (pinfunction "1_1") (pintype "passive"))
      (node (ref "P2") (pin "5") (pinfunction "5_5") (pintype "passive"))
      (node (ref "P3") (pin "5") (pinfunction "5_5") (pintype "passive"))
      (node (ref "P4") (pin "4") (pinfunction "4_4") (pintype "passive"))
      (node (ref "P5") (pin "4") (pinfunction "4_4") (pintype "passive"))
      (node (ref "P6") (pin "2") (pinfunction "2_2") (pintype "passive"))
      (node (ref "P7") (pin "1") (pintype "passive"))
      (node (ref "P7") (pin "2") (pintype "passive"))
      (node (ref "P7") (pin "3") (pintype "passive"))
      (node (ref "Q1") (pin "2") (pinfunction "E_2") (pintype "passive"))
      (node (ref "R13") (pin "1") (pinfunction "1_1") (pintype "passive"))
      (node (ref "R14") (pin "2") (pinfunction "2_2") (pintype "passive"))
      (node (ref "R25") (pin "2") (pintype "passive"))
      (node (ref "S1") (pin "2") (pinfunction "2_2") (pintype "passive"))
      (node (ref "S2") (pin "2") (pinfunction "2_2") (pintype "passive"))
      (node (ref "S3") (pin "2") (pinfunction "2_2") (pintype "passive"))
      (node (ref "S4") (pin "2") (pinfunction "2_2") (pintype "passive"))
      (node (ref "S5") (pin "2") (pinfunction "2_2") (pintype "passive"))
      (node (ref "S6") (pin "2") (pinfunction "2_2") (pintype "passive"))
      (node (ref "S7") (pin "2") (pinfunction "2_2") (pintype "passive"))
      (node (ref "STM1") (pin "10") (pinfunction "VSS_5_10") (pintype "passive"))
      (node (ref "STM1") (pin "27") (pinfunction "VSS_4_27") (pintype "passive"))
      (node (ref "STM1") (pin "49") (pinfunction "VSS_1_49") (pintype "passive"))
      (node (ref "STM1") (pin "74") (pinfunction "VSS_2_74") (pintype "passive"))
      (node (ref "STM1") (pin "99") (pinfunction "VSS_3_99") (pintype "passive"))
      (node (ref "U3") (pin "13") (pinfunction "GND_13") (pintype "passive"))
      (node (ref "U3") (pin "21") (pinfunction "GND_21") (pintype "passive"))
      (node (ref "U5") (pin "1") (pinfunction "GND_1") (pintype "passive"))
      (node (ref "U6") (pin "5") (pintype "passive"))
      (node (ref "U6") (pin "6") (pintype "passive"))
      (node (ref "U6") (pin "7") (pintype "passive"))
      (node (ref "U6") (pin "8") (pintype "passive"))
      (node (ref "U7") (pin "2") (pinfunction "GND_2") (pintype "passive"))
      (node (ref "U8") (pin "2") (pinfunction "GND_2") (pintype "passive"))
      (node (ref "USB1") (pin "5") (pinfunction "5_5") (pintype "passive"))
      (node (ref "USB2") (pin "5") (pinfunction "5_5") (pintype "passive"))
      (node (ref "W1") (pin "16") (pinfunction "GND_16") (pintype "passive"))
    )
    (net (code "56") (name "GNDA") (class "Default")
      (node (ref "C10") (pin "2") (pinfunction "2_2") (pintype "passive"))
      (node (ref "C11") (pin "1") (pintype "passive"))
      (node (ref "C12") (pin "1") (pintype "passive"))
      (node (ref "C14") (pin "2") (pinfunction "2_2") (pintype "passive"))
      (node (ref "C15") (pin "1") (pinfunction "1_1") (pintype "passive"))
      (node (ref "C16") (pin "1") (pinfunction "1_1") (pintype "passive"))
      (node (ref "C17") (pin "2") (pinfunction "2_2") (pintype "passive"))
      (node (ref "C2") (pin "1") (pintype "passive"))
      (node (ref "C5") (pin "2") (pintype "passive"))
      (node (ref "C7") (pin "1") (pintype "passive"))
      (node (ref "C9") (pin "1") (pintype "passive"))
      (node (ref "R13") (pin "2") (pinfunction "2_2") (pintype "passive"))
      (node (ref "R15") (pin "1") (pinfunction "1_1") (pintype "passive"))
      (node (ref "STM1") (pin "19") (pinfunction "VSSA_19") (pintype "passive"))
      (node (ref "STM1") (pin "20") (pinfunction "VREF-_20") (pintype "passive"))
      (node (ref "U1") (pin "10") (pinfunction "PGND3_10") (pintype "passive"))
      (node (ref "U1") (pin "18") (pinfunction "GND_18") (pintype "passive"))
      (node (ref "U1") (pin "3") (pinfunction "PGND1_3") (pintype "passive"))
      (node (ref "U1") (pin "4") (pinfunction "PGND1_4") (pintype "passive"))
      (node (ref "U1") (pin "9") (pinfunction "PGND2_9") (pintype "passive"))
      (node (ref "U2") (pin "1") (pinfunction "CLKIN_1") (pintype "passive"))
      (node (ref "U2") (pin "11") (pinfunction "FSYNC_11") (pintype "passive"))
      (node (ref "U2") (pin "18") (pinfunction "GND_18") (pintype "passive"))
      (node (ref "U4") (pin "2") (pinfunction "V-_2") (pintype "passive"))
    )
    (net (code "57") (name "Net-(C17-Pad1)") (class "Default")
      (node (ref "C17") (pin "1") (pinfunction "1_1") (pintype "passive"))
      (node (ref "R10") (pin "1") (pinfunction "1_1") (pintype "passive"))
      (node (ref "R12") (pin "1") (pinfunction "1_1") (pintype "passive"))
      (node (ref "R15") (pin "2") (pinfunction "2_2") (pintype "passive"))
    )
    (net (code "58") (name "Net-(D1-A)") (class "Default")
      (node (ref "D1") (pin "1") (pinfunction "A_1") (pintype "passive"))
      (node (ref "R6") (pin "1") (pintype "passive"))
    )
    (net (code "59") (name "Net-(D2-A)") (class "Default")
      (node (ref "D2") (pin "1") (pinfunction "A_1") (pintype "passive"))
      (node (ref "R8") (pin "1") (pintype "passive"))
    )
    (net (code "60") (name "Net-(D3-K)") (class "Default")
      (node (ref "D3") (pin "2") (pinfunction "K_2") (pintype "passive"))
      (node (ref "R26") (pin "2") (pinfunction "2_2") (pintype "passive"))
    )
    (net (code "61") (name "Net-(D4-K)") (class "Default")
      (node (ref "D4") (pin "2") (pinfunction "K_2") (pintype "passive"))
      (node (ref "R27") (pin "2") (pinfunction "2_2") (pintype "passive"))
    )
    (net (code "62") (name "Net-(D5-K)") (class "Default")
      (node (ref "D5") (pin "2") (pinfunction "K_2") (pintype "passive"))
      (node (ref "R28") (pin "2") (pinfunction "2_2") (pintype "passive"))
    )
    (net (code "63") (name "Net-(D6-K)") (class "Default")
      (node (ref "D6") (pin "2") (pinfunction "K_2") (pintype "passive"))
      (node (ref "R29") (pin "2") (pinfunction "2_2") (pintype "passive"))
    )
    (net (code "64") (name "Net-(D7-A)") (class "Default")
      (node (ref "D7") (pin "1") (pinfunction "A_1") (pintype "passive"))
      (node (ref "R33") (pin "1") (pinfunction "1_1") (pintype "passive"))
    )
    (net (code "65") (name "Net-(D8-A)") (class "Default")
      (node (ref "D8") (pin "1") (pinfunction "A_1") (pintype "passive"))
      (node (ref "R34") (pin "1") (pinfunction "1_1") (pintype "passive"))
    )
    (net (code "66") (name "Net-(P7-O)") (class "Default")
      (node (ref "P7") (pin "0") (pinfunction "O_0") (pintype "passive"))
      (node (ref "W1") (pin "17") (pinfunction "ANT-2.4G_17") (pintype "passive"))
    )
    (net (code "67") (name "Net-(Q1-B)") (class "Default")
      (node (ref "Q1") (pin "1") (pinfunction "B_1") (pintype "passive"))
      (node (ref "R24") (pin "2") (pintype "passive"))
      (node (ref "R25") (pin "1") (pintype "passive"))
    )
    (net (code "68") (name "Net-(Q1-C)") (class "Default")
      (node (ref "LS1") (pin "2") (pinfunction "2_2") (pintype "passive"))
      (node (ref "Q1") (pin "3") (pinfunction "C_3") (pintype "passive"))
    )
    (net (code "69") (name "Net-(R10-Pad2)") (class "Default")
      (node (ref "R10") (pin "2") (pinfunction "2_2") (pintype "passive"))
      (node (ref "R9") (pin "1") (pinfunction "1_1") (pintype "passive"))
    )
    (net (code "70") (name "Net-(STM1-BOOT0)") (class "Default")
      (node (ref "R2") (pin "2") (pinfunction "2_2") (pintype "passive"))
      (node (ref "STM1") (pin "94") (pinfunction "BOOT0_94") (pintype "passive"))
    )
    (net (code "71") (name "Net-(STM1-OSC_IN)") (class "Default")
      (node (ref "C8") (pin "2") (pinfunction "2_2") (pintype "passive"))
      (node (ref "STM1") (pin "12") (pinfunction "OSC_IN_12") (pintype "passive"))
      (node (ref "XT1") (pin "1") (pinfunction "OSC1_1") (pintype "passive"))
    )
    (net (code "72") (name "Net-(STM1-OSC_OUT)") (class "Default")
      (node (ref "C13") (pin "2") (pinfunction "2_2") (pintype "passive"))
      (node (ref "STM1") (pin "13") (pinfunction "OSC_OUT_13") (pintype "passive"))
      (node (ref "XT1") (pin "2") (pinfunction "OSC2_2") (pintype "passive"))
    )
    (net (code "73") (name "Net-(U2-CPOUT)") (class "Default")
      (node (ref "C2") (pin "2") (pintype "passive"))
      (node (ref "U2") (pin "20") (pinfunction "CPOUT_20") (pintype "passive"))
    )
    (net (code "74") (name "Net-(U2-REGOUT)") (class "Default")
      (node (ref "C12") (pin "2") (pintype "passive"))
      (node (ref "U2") (pin "10") (pinfunction "REGOUT_10") (pintype "passive"))
    )
    (net (code "75") (name "Net-(U3-PIO8)") (class "Default")
      (node (ref "R8") (pin "2") (pintype "passive"))
      (node (ref "U3") (pin "31") (pinfunction "PIO8_31") (pintype "passive"))
    )
    (net (code "76") (name "Net-(U3-PIO9)") (class "Default")
      (node (ref "R6") (pin "2") (pintype "passive"))
      (node (ref "U3") (pin "32") (pinfunction "PIO9_32") (pintype "passive"))
    )
    (net (code "77") (name "Net-(U3-PIO11)") (class "Default")
      (node (ref "R5") (pin "2") (pintype "passive"))
      (node (ref "S2") (pin "1") (pinfunction "1_1") (pintype "passive"))
      (node (ref "U3") (pin "34") (pinfunction "PIO11_34") (pintype "passive"))
    )
    (net (code "78") (name "Net-(U4-+IN)") (class "Default")
      (node (ref "R12") (pin "2") (pinfunction "2_2") (pintype "passive"))
      (node (ref "U4") (pin "3") (pinfunction "+IN_3") (pintype "passive"))
    )
    (net (code "79") (name "Net-(U4--IN)") (class "Default")
      (node (ref "R7") (pin "1") (pinfunction "1_1") (pintype "passive"))
      (node (ref "U4") (pin "4") (pinfunction "-IN_4") (pintype "passive"))
    )
    (net (code "80") (name "Net-(U4-OUT)") (class "Default")
      (node (ref "R11") (pin "1") (pinfunction "1_1") (pintype "passive"))
      (node (ref "U4") (pin "1") (pinfunction "OUT_1") (pintype "passive"))
    )
    (net (code "81") (name "Net-(U7-BYP)") (class "Default")
      (node (ref "C28") (pin "2") (pinfunction "2_2") (pintype "passive"))
      (node (ref "U7") (pin "4") (pinfunction "BYP_4") (pintype "passive"))
    )
    (net (code "82") (name "Net-(U8-BYP)") (class "Default")
      (node (ref "C34") (pin "2") (pinfunction "2_2") (pintype "passive"))
      (node (ref "U8") (pin "4") (pinfunction "BYP_4") (pintype "passive"))
    )
    (net (code "83") (name "VCC_3.3V") (class "Default")
      (node (ref "C1") (pin "1") (pinfunction "1_1") (pintype "passive"))
      (node (ref "C18") (pin "2") (pinfunction "2_2") (pintype "passive"))
      (node (ref "C19") (pin "2") (pinfunction "2_2") (pintype "passive"))
      (node (ref "C27") (pin "2") (pinfunction "2_2") (pintype "passive"))
      (node (ref "C4") (pin "2") (pinfunction "2_2") (pintype "passive"))
      (node (ref "C6") (pin "1") (pintype "passive"))
      (node (ref "D3") (pin "1") (pinfunction "A_1") (pintype "passive"))
      (node (ref "D4") (pin "1") (pinfunction "A_1") (pintype "passive"))
      (node (ref "D5") (pin "1") (pinfunction "A_1") (pintype "passive"))
      (node (ref "D6") (pin "1") (pinfunction "A_1") (pintype "passive"))
      (node (ref "L1") (pin "1") (pinfunction "1_1") (pintype "passive"))
      (node (ref "P1") (pin "3") (pinfunction "3_3") (pintype "passive"))
      (node (ref "R1") (pin "1") (pinfunction "1_1") (pintype "passive"))
      (node (ref "R16") (pin "2") (pinfunction "2_2") (pintype "passive"))
      (node (ref "R17") (pin "2") (pinfunction "2_2") (pintype "passive"))
      (node (ref "R18") (pin "2") (pinfunction "2_2") (pintype "passive"))
      (node (ref "R19") (pin "1") (pinfunction "1_1") (pintype "passive"))
      (node (ref "R20") (pin "2") (pinfunction "2_2") (pintype "passive"))
      (node (ref "R21") (pin "2") (pinfunction "2_2") (pintype "passive"))
      (node (ref "R22") (pin "2") (pinfunction "2_2") (pintype "passive"))
      (node (ref "R23") (pin "1") (pinfunction "1_1") (pintype "passive"))
      (node (ref "R5") (pin "1") (pintype "passive"))
      (node (ref "STM1") (pin "100") (pinfunction "VDD_3_100") (pintype "passive"))
      (node (ref "STM1") (pin "11") (pinfunction "VDD_5_11") (pintype "passive"))
      (node (ref "STM1") (pin "28") (pinfunction "VDD_4_28") (pintype "passive"))
      (node (ref "STM1") (pin "50") (pinfunction "VDD_1_50") (pintype "passive"))
      (node (ref "STM1") (pin "75") (pinfunction "VDD_2_75") (pintype "passive"))
      (node (ref "U3") (pin "12") (pinfunction "3V3_12") (pintype "passive"))
      (node (ref "U7") (pin "5") (pinfunction "V_OUT_5") (pintype "passive"))
    )
    (net (code "84") (name "VCC_5V") (class "Default")
      (node (ref "C22") (pin "1") (pintype "passive"))
      (node (ref "C23") (pin "2") (pintype "passive"))
      (node (ref "C24") (pin "2") (pintype "passive"))
      (node (ref "C25") (pin "2") (pintype "passive"))
      (node (ref "C26") (pin "2") (pinfunction "2_2") (pintype "passive"))
      (node (ref "C30") (pin "2") (pinfunction "2_2") (pintype "passive"))
      (node (ref "C5") (pin "1") (pintype "passive"))
      (node (ref "LS1") (pin "1") (pinfunction "1_1") (pintype "passive"))
      (node (ref "P2") (pin "2") (pinfunction "2_2") (pintype "passive"))
      (node (ref "P3") (pin "2") (pinfunction "2_2") (pintype "passive"))
      (node (ref "P4") (pin "1") (pinfunction "1_1") (pintype "passive"))
      (node (ref "P5") (pin "3") (pinfunction "3_3") (pintype "passive"))
      (node (ref "U1") (pin "19") (pinfunction "STBY_19") (pintype "passive"))
      (node (ref "U1") (pin "20") (pinfunction "VCC_20") (pintype "passive"))
      (node (ref "U5") (pin "2") (pinfunction "OUT_2") (pintype "passive"))
      (node (ref "U5") (pin "4") (pinfunction "OUT_4") (pintype "passive"))
      (node (ref "U7") (pin "1") (pinfunction "V_IN_1") (pintype "passive"))
      (node (ref "U7") (pin "3") (pinfunction "EN_3") (pintype "passive"))
      (node (ref "U8") (pin "1") (pinfunction "V_IN_1") (pintype "passive"))
      (node (ref "U8") (pin "3") (pinfunction "EN_3") (pintype "passive"))
    )
    (net (code "85") (name "unconnected-(STM1-NC-Pad73)") (class "Default")
      (node (ref "STM1") (pin "73") (pinfunction "NC_73") (pintype "passive"))
    )
    (net (code "86") (name "unconnected-(STM1-PA1-Pad24)") (class "Default")
      (node (ref "STM1") (pin "24") (pinfunction "PA1_24") (pintype "passive"))
    )
    (net (code "87") (name "unconnected-(STM1-PA4-Pad29)") (class "Default")
      (node (ref "STM1") (pin "29") (pinfunction "PA4_29") (pintype "passive"))
    )
    (net (code "88") (name "unconnected-(STM1-PA5-Pad30)") (class "Default")
      (node (ref "STM1") (pin "30") (pinfunction "PA5_30") (pintype "passive"))
    )
    (net (code "89") (name "unconnected-(STM1-PA6-Pad31)") (class "Default")
      (node (ref "STM1") (pin "31") (pinfunction "PA6_31") (pintype "passive"))
    )
    (net (code "90") (name "unconnected-(STM1-PA7-Pad32)") (class "Default")
      (node (ref "STM1") (pin "32") (pinfunction "PA7_32") (pintype "passive"))
    )
    (net (code "91") (name "unconnected-(STM1-PB0-Pad35)") (class "Default")
      (node (ref "STM1") (pin "35") (pinfunction "PB0_35") (pintype "passive"))
    )
    (net (code "92") (name "unconnected-(STM1-PB1-Pad36)") (class "Default")
      (node (ref "STM1") (pin "36") (pinfunction "PB1_36") (pintype "passive"))
    )
    (net (code "93") (name "unconnected-(STM1-PB4-Pad90)") (class "Default")
      (node (ref "STM1") (pin "90") (pinfunction "PB4_90") (pintype "passive"))
    )
    (net (code "94") (name "unconnected-(STM1-PB5-Pad91)") (class "Default")
      (node (ref "STM1") (pin "91") (pinfunction "PB5_91") (pintype "passive"))
    )
    (net (code "95") (name "unconnected-(STM1-PC0-Pad15)") (class "Default")
      (node (ref "STM1") (pin "15") (pinfunction "PC0_15") (pintype "passive"))
    )
    (net (code "96") (name "unconnected-(STM1-PC1-Pad16)") (class "Default")
      (node (ref "STM1") (pin "16") (pinfunction "PC1_16") (pintype "passive"))
    )
    (net (code "97") (name "unconnected-(STM1-PC2-Pad17)") (class "Default")
      (node (ref "STM1") (pin "17") (pinfunction "PC2_17") (pintype "passive"))
    )
    (net (code "98") (name "unconnected-(STM1-PC3-Pad18)") (class "Default")
      (node (ref "STM1") (pin "18") (pinfunction "PC3_18") (pintype "passive"))
    )
    (net (code "99") (name "unconnected-(STM1-PC4-Pad33)") (class "Default")
      (node (ref "STM1") (pin "33") (pinfunction "PC4_33") (pintype "passive"))
    )
    (net (code "100") (name "unconnected-(STM1-PC5-Pad34)") (class "Default")
      (node (ref "STM1") (pin "34") (pinfunction "PC5_34") (pintype "passive"))
    )
    (net (code "101") (name "unconnected-(STM1-PC12-Pad80)") (class "Default")
      (node (ref "STM1") (pin "80") (pinfunction "PC12_80") (pintype "passive"))
    )
    (net (code "102") (name "unconnected-(STM1-PC13-Pad7)") (class "Default")
      (node (ref "STM1") (pin "7") (pinfunction "PC13_7") (pintype "passive"))
    )
    (net (code "103") (name "unconnected-(STM1-PC14-Pad8)") (class "Default")
      (node (ref "STM1") (pin "8") (pinfunction "PC14_8") (pintype "passive"))
    )
    (net (code "104") (name "unconnected-(STM1-PC15-Pad9)") (class "Default")
      (node (ref "STM1") (pin "9") (pinfunction "PC15_9") (pintype "passive"))
    )
    (net (code "105") (name "unconnected-(STM1-PD0-Pad81)") (class "Default")
      (node (ref "STM1") (pin "81") (pinfunction "PD0_81") (pintype "passive"))
    )
    (net (code "106") (name "unconnected-(STM1-PD1-Pad82)") (class "Default")
      (node (ref "STM1") (pin "82") (pinfunction "PD1_82") (pintype "passive"))
    )
    (net (code "107") (name "unconnected-(STM1-PD2-Pad83)") (class "Default")
      (node (ref "STM1") (pin "83") (pinfunction "PD2_83") (pintype "passive"))
    )
    (net (code "108") (name "unconnected-(STM1-PD3-Pad84)") (class "Default")
      (node (ref "STM1") (pin "84") (pinfunction "PD3_84") (pintype "passive"))
    )
    (net (code "109") (name "unconnected-(STM1-PD4-Pad85)") (class "Default")
      (node (ref "STM1") (pin "85") (pinfunction "PD4_85") (pintype "passive"))
    )
    (net (code "110") (name "unconnected-(STM1-PD5-Pad86)") (class "Default")
      (node (ref "STM1") (pin "86") (pinfunction "PD5_86") (pintype "passive"))
    )
    (net (code "111") (name "unconnected-(STM1-PD7-Pad88)") (class "Default")
      (node (ref "STM1") (pin "88") (pinfunction "PD7_88") (pintype "passive"))
    )
    (net (code "112") (name "unconnected-(STM1-PD8-Pad55)") (class "Default")
      (node (ref "STM1") (pin "55") (pinfunction "PD8_55") (pintype "passive"))
    )
    (net (code "113") (name "unconnected-(STM1-PD9-Pad56)") (class "Default")
      (node (ref "STM1") (pin "56") (pinfunction "PD9_56") (pintype "passive"))
    )
    (net (code "114") (name "unconnected-(STM1-PD10-Pad57)") (class "Default")
      (node (ref "STM1") (pin "57") (pinfunction "PD10_57") (pintype "passive"))
    )
    (net (code "115") (name "unconnected-(STM1-PE0-Pad97)") (class "Default")
      (node (ref "STM1") (pin "97") (pinfunction "PE0_97") (pintype "passive"))
    )
    (net (code "116") (name "unconnected-(STM1-PE1-Pad98)") (class "Default")
      (node (ref "STM1") (pin "98") (pinfunction "PE1_98") (pintype "passive"))
    )
    (net (code "117") (name "unconnected-(STM1-PE2-Pad1)") (class "Default")
      (node (ref "STM1") (pin "1") (pinfunction "PE2_1") (pintype "passive"))
    )
    (net (code "118") (name "unconnected-(STM1-PE3-Pad2)") (class "Default")
      (node (ref "STM1") (pin "2") (pinfunction "PE3_2") (pintype "passive"))
    )
    (net (code "119") (name "unconnected-(STM1-PE4-Pad3)") (class "Default")
      (node (ref "STM1") (pin "3") (pinfunction "PE4_3") (pintype "passive"))
    )
    (net (code "120") (name "unconnected-(STM1-PE5-Pad4)") (class "Default")
      (node (ref "STM1") (pin "4") (pinfunction "PE5_4") (pintype "passive"))
    )
    (net (code "121") (name "unconnected-(STM1-PE6-Pad5)") (class "Default")
      (node (ref "STM1") (pin "5") (pinfunction "PE6_5") (pintype "passive"))
    )
    (net (code "122") (name "unconnected-(STM1-PE15-Pad46)") (class "Default")
      (node (ref "STM1") (pin "46") (pinfunction "PE15_46") (pintype "passive"))
    )
    (net (code "123") (name "unconnected-(STM1-VBAT-Pad6)") (class "Default")
      (node (ref "STM1") (pin "6") (pinfunction "VBAT_6") (pintype "passive"))
    )
    (net (code "124") (name "unconnected-(U2-AD0-Pad9)") (class "Default")
      (node (ref "U2") (pin "9") (pinfunction "AD0_9") (pintype "passive+no_connect"))
    )
    (net (code "125") (name "unconnected-(U2-AUX_CL-Pad7)") (class "Default")
      (node (ref "U2") (pin "7") (pinfunction "AUX_CL_7") (pintype "passive+no_connect"))
    )
    (net (code "126") (name "unconnected-(U2-AUX_DA-Pad6)") (class "Default")
      (node (ref "U2") (pin "6") (pinfunction "AUX_DA_6") (pintype "passive+no_connect"))
    )
    (net (code "127") (name "unconnected-(U2-CLKOUT-Pad22)") (class "Default")
      (node (ref "U2") (pin "22") (pinfunction "CLKOUT_22") (pintype "passive+no_connect"))
    )
    (net (code "128") (name "unconnected-(U2-INT-Pad12)") (class "Default")
      (node (ref "U2") (pin "12") (pinfunction "INT_12") (pintype "passive"))
    )
    (net (code "129") (name "unconnected-(U2-Pad2)") (class "Default")
      (node (ref "U2") (pin "2") (pinfunction "2_2") (pintype "passive+no_connect"))
    )
    (net (code "130") (name "unconnected-(U2-Pad3)") (class "Default")
      (node (ref "U2") (pin "3") (pinfunction "3_3") (pintype "passive+no_connect"))
    )
    (net (code "131") (name "unconnected-(U2-Pad4)") (class "Default")
      (node (ref "U2") (pin "4") (pinfunction "4_4") (pintype "passive+no_connect"))
    )
    (net (code "132") (name "unconnected-(U2-Pad5)") (class "Default")
      (node (ref "U2") (pin "5") (pinfunction "5_5") (pintype "passive+no_connect"))
    )
    (net (code "133") (name "unconnected-(U2-Pad14)") (class "Default")
      (node (ref "U2") (pin "14") (pinfunction "14_14") (pintype "passive+no_connect"))
    )
    (net (code "134") (name "unconnected-(U2-Pad15)") (class "Default")
      (node (ref "U2") (pin "15") (pinfunction "15_15") (pintype "passive+no_connect"))
    )
    (net (code "135") (name "unconnected-(U2-Pad16)") (class "Default")
      (node (ref "U2") (pin "16") (pinfunction "16_16") (pintype "passive+no_connect"))
    )
    (net (code "136") (name "unconnected-(U2-Pad17)") (class "Default")
      (node (ref "U2") (pin "17") (pinfunction "17_17") (pintype "passive+no_connect"))
    )
    (net (code "137") (name "unconnected-(U2-RESV-Pad19)") (class "Default")
      (node (ref "U2") (pin "19") (pinfunction "RESV_19") (pintype "passive+no_connect"))
    )
    (net (code "138") (name "unconnected-(U2-RESV-Pad21)") (class "Default")
      (node (ref "U2") (pin "21") (pinfunction "RESV_21") (pintype "passive+no_connect"))
    )
    (net (code "139") (name "unconnected-(U3-AIN0-Pad9)") (class "Default")
      (node (ref "U3") (pin "9") (pinfunction "AIN0_9") (pintype "passive+no_connect"))
    )
    (net (code "140") (name "unconnected-(U3-AIN1-Pad10)") (class "Default")
      (node (ref "U3") (pin "10") (pinfunction "AIN1_10") (pintype "passive+no_connect"))
    )
    (net (code "141") (name "unconnected-(U3-CLK-Pad19)") (class "Default")
      (node (ref "U3") (pin "19") (pinfunction "CLK_19") (pintype "passive+no_connect"))
    )
    (net (code "142") (name "unconnected-(U3-CON-Pad22)") (class "Default")
      (node (ref "U3") (pin "22") (pinfunction "CON_22") (pintype "passive+no_connect"))
    )
    (net (code "143") (name "unconnected-(U3-CSB-Pad16)") (class "Default")
      (node (ref "U3") (pin "16") (pinfunction "CSB_16") (pintype "passive+no_connect"))
    )
    (net (code "144") (name "unconnected-(U3-CTS-Pad3)") (class "Default")
      (node (ref "U3") (pin "3") (pinfunction "CTS_3") (pintype "passive+no_connect"))
    )
    (net (code "145") (name "unconnected-(U3-MOSI-Pad17)") (class "Default")
      (node (ref "U3") (pin "17") (pinfunction "MOSI_17") (pintype "passive+no_connect"))
    )
    (net (code "146") (name "unconnected-(U3-MOSO-Pad18)") (class "Default")
      (node (ref "U3") (pin "18") (pinfunction "MOSO_18") (pintype "passive+no_connect"))
    )
    (net (code "147") (name "unconnected-(U3-NC-Pad14)") (class "Default")
      (node (ref "U3") (pin "14") (pinfunction "NC_14") (pintype "passive+no_connect"))
    )
    (net (code "148") (name "unconnected-(U3-PCM_CLK-Pad5)") (class "Default")
      (node (ref "U3") (pin "5") (pinfunction "PCM_CLK_5") (pintype "passive+no_connect"))
    )
    (net (code "149") (name "unconnected-(U3-PCM_IN-Pad7)") (class "Default")
      (node (ref "U3") (pin "7") (pinfunction "PCM_IN_7") (pintype "passive+no_connect"))
    )
    (net (code "150") (name "unconnected-(U3-PCM_OUT-Pad6)") (class "Default")
      (node (ref "U3") (pin "6") (pinfunction "PCM_OUT_6") (pintype "passive+no_connect"))
    )
    (net (code "151") (name "unconnected-(U3-PCM_SYNC-Pad8)") (class "Default")
      (node (ref "U3") (pin "8") (pinfunction "PCM_SYNC_8") (pintype "passive+no_connect"))
    )
    (net (code "152") (name "unconnected-(U3-PIO0-Pad23)") (class "Default")
      (node (ref "U3") (pin "23") (pinfunction "PIO0_23") (pintype "passive+no_connect"))
    )
    (net (code "153") (name "unconnected-(U3-PIO1-Pad24)") (class "Default")
      (node (ref "U3") (pin "24") (pinfunction "PIO1_24") (pintype "passive+no_connect"))
    )
    (net (code "154") (name "unconnected-(U3-PIO2-Pad25)") (class "Default")
      (node (ref "U3") (pin "25") (pinfunction "PIO2_25") (pintype "passive+no_connect"))
    )
    (net (code "155") (name "unconnected-(U3-PIO3-Pad26)") (class "Default")
      (node (ref "U3") (pin "26") (pinfunction "PIO3_26") (pintype "passive+no_connect"))
    )
    (net (code "156") (name "unconnected-(U3-PIO4-Pad27)") (class "Default")
      (node (ref "U3") (pin "27") (pinfunction "PIO4_27") (pintype "passive+no_connect"))
    )
    (net (code "157") (name "unconnected-(U3-PIO5-Pad28)") (class "Default")
      (node (ref "U3") (pin "28") (pinfunction "PIO5_28") (pintype "passive+no_connect"))
    )
    (net (code "158") (name "unconnected-(U3-PIO6-Pad29)") (class "Default")
      (node (ref "U3") (pin "29") (pinfunction "PIO6_29") (pintype "passive+no_connect"))
    )
    (net (code "159") (name "unconnected-(U3-PIO7-Pad30)") (class "Default")
      (node (ref "U3") (pin "30") (pinfunction "PIO7_30") (pintype "passive+no_connect"))
    )
    (net (code "160") (name "unconnected-(U3-PIO10-Pad33)") (class "Default")
      (node (ref "U3") (pin "33") (pinfunction "PIO10_33") (pintype "passive+no_connect"))
    )
    (net (code "161") (name "unconnected-(U3-RST-Pad11)") (class "Default")
      (node (ref "U3") (pin "11") (pinfunction "RST_11") (pintype "passive+no_connect"))
    )
    (net (code "162") (name "unconnected-(U3-RTS-Pad4)") (class "Default")
      (node (ref "U3") (pin "4") (pinfunction "RTS_4") (pintype "passive+no_connect"))
    )
    (net (code "163") (name "unconnected-(U3-USB_D+-Pad20)") (class "Default")
      (node (ref "U3") (pin "20") (pinfunction "USB_D+_20") (pintype "passive+no_connect"))
    )
    (net (code "164") (name "unconnected-(U3-USB_D--Pad15)") (class "Default")
      (node (ref "U3") (pin "15") (pinfunction "USB_D-_15") (pintype "passive+no_connect"))
    )
    (net (code "165") (name "unconnected-(USB1-Pad1)") (class "Default")
      (node (ref "USB1") (pin "1") (pinfunction "1_1") (pintype "passive"))
    )
    (net (code "166") (name "unconnected-(USB1-Pad4)") (class "Default")
      (node (ref "USB1") (pin "4") (pinfunction "4_4") (pintype "passive"))
    )
    (net (code "167") (name "unconnected-(USB1-Pad6)") (class "Default")
      (node (ref "USB1") (pin "6") (pinfunction "6_6") (pintype "passive"))
    )
    (net (code "168") (name "unconnected-(USB1-Pad7)") (class "Default")
      (node (ref "USB1") (pin "7") (pinfunction "7_7") (pintype "passive"))
    )
    (net (code "169") (name "unconnected-(USB1-Pad8)") (class "Default")
      (node (ref "USB1") (pin "8") (pinfunction "8_8") (pintype "passive"))
    )
    (net (code "170") (name "unconnected-(USB1-Pad9)") (class "Default")
      (node (ref "USB1") (pin "9") (pinfunction "9_9") (pintype "passive"))
    )
    (net (code "171") (name "unconnected-(USB2-Pad1)") (class "Default")
      (node (ref "USB2") (pin "1") (pinfunction "1_1") (pintype "passive"))
    )
    (net (code "172") (name "unconnected-(USB2-Pad4)") (class "Default")
      (node (ref "USB2") (pin "4") (pinfunction "4_4") (pintype "passive"))
    )
    (net (code "173") (name "unconnected-(USB2-Pad6)") (class "Default")
      (node (ref "USB2") (pin "6") (pinfunction "6_6") (pintype "passive"))
    )
    (net (code "174") (name "unconnected-(USB2-Pad7)") (class "Default")
      (node (ref "USB2") (pin "7") (pinfunction "7_7") (pintype "passive"))
    )
    (net (code "175") (name "unconnected-(USB2-Pad8)") (class "Default")
      (node (ref "USB2") (pin "8") (pinfunction "8_8") (pintype "passive"))
    )
    (net (code "176") (name "unconnected-(USB2-Pad9)") (class "Default")
      (node (ref "USB2") (pin "9") (pinfunction "9_9") (pintype "passive"))
    )
    (net (code "177") (name "unconnected-(W1-GPIO9-Pad9)") (class "Default")
      (node (ref "W1") (pin "9") (pinfunction "GPIO9_9") (pintype "passive"))
    )
    (net (code "178") (name "unconnected-(W1-NC-Pad1)") (class "Default")
      (node (ref "W1") (pin "1") (pinfunction "NC_1") (pintype "passive"))
    )
    (net (code "179") (name "unconnected-(W1-NC-Pad2)") (class "Default")
      (node (ref "W1") (pin "2") (pinfunction "NC_2") (pintype "passive"))
    )
    (net (code "180") (name "unconnected-(W1-NC-Pad3)") (class "Default")
      (node (ref "W1") (pin "3") (pinfunction "NC_3") (pintype "passive"))
    )
    (net (code "181") (name "unconnected-(W1-NC-Pad4)") (class "Default")
      (node (ref "W1") (pin "4") (pinfunction "NC_4") (pintype "passive"))
    )
    (net (code "182") (name "unconnected-(W1-UART0-CTS-Pad7)") (class "Default")
      (node (ref "W1") (pin "7") (pinfunction "UART0-CTS_7") (pintype "passive"))
    )
    (net (code "183") (name "unconnected-(W1-UART0-RTS-Pad8)") (class "Default")
      (node (ref "W1") (pin "8") (pinfunction "UART0-RTS_8") (pintype "passive"))
    )
  )
)
